# UnoRover.net
KiCad netlist of a schematic drawn in EAGLE
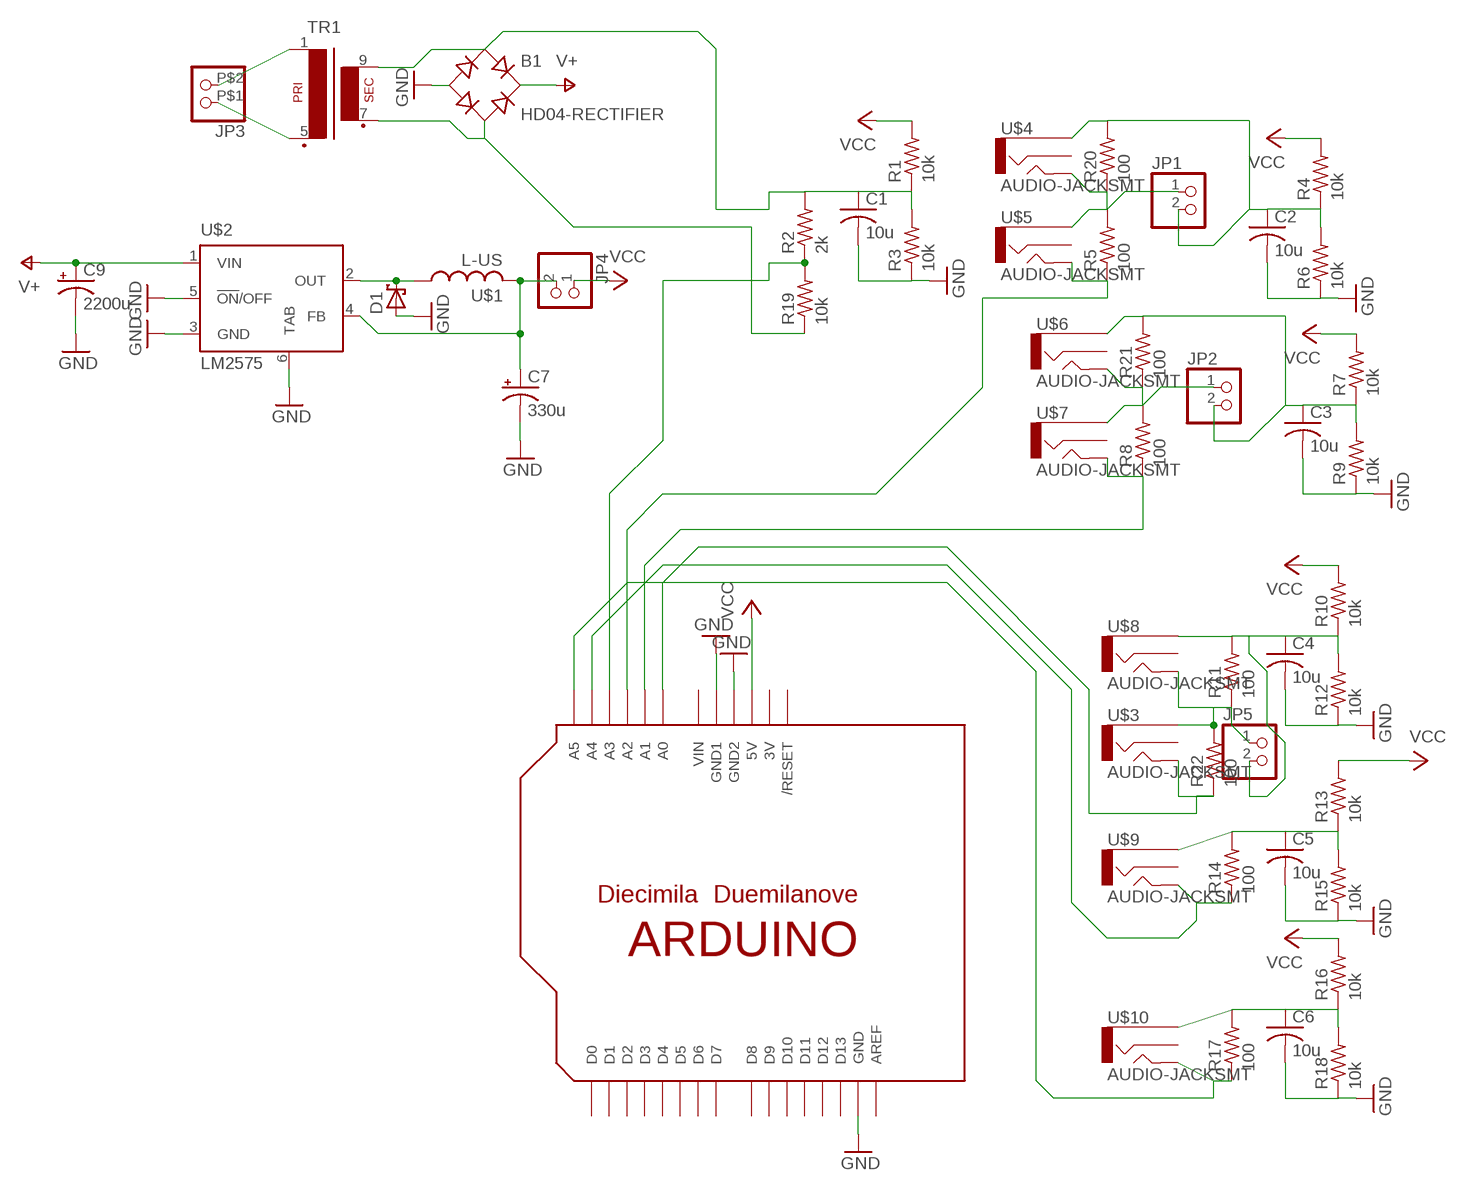
[diagram p0: schematic, sheet 1]

(export (version "E")
  (design (tool "Eeschema 10.0.6"))
  (components
    (comp (ref "B1")
      (value "HD04-RECTIFIER")
      (footprint "eagle-import:MINIDIP-4")
      (libsource (lib "eagle-import") (part "HD04-RECTIFIER"))
    )
    (comp (ref "C1")
      (value "10u")
      (footprint "eagle-import:C0805")
      (libsource (lib "eagle-import") (part "C-USC0805"))
    )
    (comp (ref "C2")
      (value "10u")
      (footprint "eagle-import:C0805")
      (libsource (lib "eagle-import") (part "C-USC0805"))
    )
    (comp (ref "C3")
      (value "10u")
      (footprint "eagle-import:C0805")
      (libsource (lib "eagle-import") (part "C-USC0805"))
    )
    (comp (ref "C4")
      (value "10u")
      (footprint "eagle-import:C0805")
      (libsource (lib "eagle-import") (part "C-USC0805"))
    )
    (comp (ref "C5")
      (value "10u")
      (footprint "eagle-import:C0805")
      (libsource (lib "eagle-import") (part "C-USC0805"))
    )
    (comp (ref "C6")
      (value "10u")
      (footprint "eagle-import:C0805")
      (libsource (lib "eagle-import") (part "C-USC0805"))
    )
    (comp (ref "C7")
      (value "330u")
      (footprint "eagle-import:E3,5-8")
      (libsource (lib "eagle-import") (part "CPOL-USE3.5-8"))
    )
    (comp (ref "C9")
      (value "2200u")
      (footprint "eagle-import:E5-13")
      (libsource (lib "eagle-import") (part "CPOL-USE5-13"))
    )
    (comp (ref "D1")
      (value "SCHOTTKY-DIODE")
      (footprint "eagle-import:SOD123FL")
      (libsource (lib "eagle-import") (part "SCHOTTKY-DIODE"))
    )
    (comp (ref "JP1")
      (value "PINHD-1X2")
      (footprint "eagle-import:1X02")
      (libsource (lib "eagle-import") (part "pinhead_PINHD-1X2"))
    )
    (comp (ref "JP2")
      (value "PINHD-1X2")
      (footprint "eagle-import:1X02")
      (libsource (lib "eagle-import") (part "pinhead_PINHD-1X2"))
    )
    (comp (ref "JP3")
      (value "PINHD-1X25MM_TERMINAL")
      (footprint "eagle-import:5MM_TERMINAL")
      (libsource (lib "eagle-import") (part "PINHD-1X25MM_TERMINAL"))
    )
    (comp (ref "JP4")
      (value "PINHD-1X2")
      (footprint "eagle-import:1X02")
      (libsource (lib "eagle-import") (part "PINHD-1X2"))
    )
    (comp (ref "JP5")
      (value "PINHD-1X2")
      (footprint "eagle-import:1X02")
      (libsource (lib "eagle-import") (part "pinhead_PINHD-1X2"))
    )
    (comp (ref "R1")
      (value "10k")
      (footprint "eagle-import:M0805")
      (libsource (lib "eagle-import") (part "R-US_M0805"))
    )
    (comp (ref "R2")
      (value "2k")
      (footprint "eagle-import:M0805")
      (libsource (lib "eagle-import") (part "R-US_M0805"))
    )
    (comp (ref "R3")
      (value "10k")
      (footprint "eagle-import:M0805")
      (libsource (lib "eagle-import") (part "R-US_M0805"))
    )
    (comp (ref "R4")
      (value "10k")
      (footprint "eagle-import:M0805")
      (libsource (lib "eagle-import") (part "R-US_M0805"))
    )
    (comp (ref "R5")
      (value "100")
      (footprint "eagle-import:M0805")
      (libsource (lib "eagle-import") (part "R-US_M0805"))
    )
    (comp (ref "R6")
      (value "10k")
      (footprint "eagle-import:M0805")
      (libsource (lib "eagle-import") (part "R-US_M0805"))
    )
    (comp (ref "R7")
      (value "10k")
      (footprint "eagle-import:M0805")
      (libsource (lib "eagle-import") (part "R-US_M0805"))
    )
    (comp (ref "R8")
      (value "100")
      (footprint "eagle-import:M0805")
      (libsource (lib "eagle-import") (part "R-US_M0805"))
    )
    (comp (ref "R9")
      (value "10k")
      (footprint "eagle-import:M0805")
      (libsource (lib "eagle-import") (part "R-US_M0805"))
    )
    (comp (ref "R10")
      (value "10k")
      (footprint "eagle-import:M0805")
      (libsource (lib "eagle-import") (part "R-US_M0805"))
    )
    (comp (ref "R11")
      (value "100")
      (footprint "eagle-import:M0805")
      (libsource (lib "eagle-import") (part "R-US_M0805"))
    )
    (comp (ref "R12")
      (value "10k")
      (footprint "eagle-import:M0805")
      (libsource (lib "eagle-import") (part "R-US_M0805"))
    )
    (comp (ref "R13")
      (value "10k")
      (footprint "eagle-import:M0805")
      (libsource (lib "eagle-import") (part "R-US_M0805"))
    )
    (comp (ref "R14")
      (value "100")
      (footprint "eagle-import:M0805")
      (libsource (lib "eagle-import") (part "R-US_M0805"))
    )
    (comp (ref "R15")
      (value "10k")
      (footprint "eagle-import:M0805")
      (libsource (lib "eagle-import") (part "R-US_M0805"))
    )
    (comp (ref "R16")
      (value "10k")
      (footprint "eagle-import:M0805")
      (libsource (lib "eagle-import") (part "R-US_M0805"))
    )
    (comp (ref "R17")
      (value "100")
      (footprint "eagle-import:M0805")
      (libsource (lib "eagle-import") (part "R-US_M0805"))
    )
    (comp (ref "R18")
      (value "10k")
      (footprint "eagle-import:M0805")
      (libsource (lib "eagle-import") (part "R-US_M0805"))
    )
    (comp (ref "R19")
      (value "10k")
      (footprint "eagle-import:M0805")
      (libsource (lib "eagle-import") (part "R-US_M0805"))
    )
    (comp (ref "R20")
      (value "100")
      (footprint "eagle-import:M0805")
      (libsource (lib "eagle-import") (part "R-US_M0805"))
    )
    (comp (ref "R21")
      (value "100")
      (footprint "eagle-import:M0805")
      (libsource (lib "eagle-import") (part "R-US_M0805"))
    )
    (comp (ref "R22")
      (value "100")
      (footprint "eagle-import:M0805")
      (libsource (lib "eagle-import") (part "R-US_M0805"))
    )
    (comp (ref "TR1")
      (value "EI30-1")
      (footprint "eagle-import:EI30-1")
      (libsource (lib "eagle-import") (part "EI30-1"))
    )
    (comp (ref "U$1")
      (value "L-US")
      (footprint "eagle-import:INDUCTOR_MURATA")
      (libsource (lib "eagle-import") (part "L-US"))
    )
    (comp (ref "U$2")
      (value "LM2575")
      (footprint "eagle-import:TO263-5")
      (libsource (lib "eagle-import") (part "LM2575"))
    )
    (comp (ref "U$3")
      (value "AUDIO-JACKSMT")
      (footprint "eagle-import:SJ-3523-SMT-JACK")
      (libsource (lib "eagle-import") (part "AUDIO-JACKSMT"))
    )
    (comp (ref "U$4")
      (value "AUDIO-JACKSMT")
      (footprint "eagle-import:SJ-3523-SMT-JACK")
      (libsource (lib "eagle-import") (part "AUDIO-JACKSMT"))
    )
    (comp (ref "U$5")
      (value "AUDIO-JACKSMT")
      (footprint "eagle-import:SJ-3523-SMT-JACK")
      (libsource (lib "eagle-import") (part "AUDIO-JACKSMT"))
    )
    (comp (ref "U$6")
      (value "AUDIO-JACKSMT")
      (footprint "eagle-import:SJ-3523-SMT-JACK")
      (libsource (lib "eagle-import") (part "AUDIO-JACKSMT"))
    )
    (comp (ref "U$7")
      (value "AUDIO-JACKSMT")
      (footprint "eagle-import:SJ-3523-SMT-JACK")
      (libsource (lib "eagle-import") (part "AUDIO-JACKSMT"))
    )
    (comp (ref "U$8")
      (value "AUDIO-JACKSMT")
      (footprint "eagle-import:SJ-3523-SMT-JACK")
      (libsource (lib "eagle-import") (part "AUDIO-JACKSMT"))
    )
    (comp (ref "U$9")
      (value "AUDIO-JACKSMT")
      (footprint "eagle-import:SJ-3523-SMT-JACK")
      (libsource (lib "eagle-import") (part "AUDIO-JACKSMT"))
    )
    (comp (ref "U$10")
      (value "AUDIO-JACKSMT")
      (footprint "eagle-import:SJ-3523-SMT-JACK")
      (libsource (lib "eagle-import") (part "AUDIO-JACKSMT"))
    )
    (comp (ref "U$11")
      (value "ARDUINODUEMILANOVE")
      (footprint "eagle-import:ARDUINO")
      (libsource (lib "eagle-import") (part "ARDUINODUEMILANOVE"))
    )
  )
  (nets
    (net (code "1") (name "/3V") (class "Default")
      (node (ref "U$11") (pin "3V") (pinfunction "3V_3V") (pintype "power_in"))
    )
    (net (code "2") (name "/VIN") (class "Default")
      (node (ref "U$11") (pin "VIN") (pinfunction "VIN_VIN") (pintype "power_in"))
    )
    (net (code "3") (name "GND") (class "Default")
      (node (ref "B1") (pin "P$4") (pinfunction "-_P$4") (pintype "passive"))
      (node (ref "C1") (pin "2") (pinfunction "2_2") (pintype "passive"))
      (node (ref "C2") (pin "2") (pinfunction "2_2") (pintype "passive"))
      (node (ref "C3") (pin "2") (pinfunction "2_2") (pintype "passive"))
      (node (ref "C4") (pin "2") (pinfunction "2_2") (pintype "passive"))
      (node (ref "C5") (pin "2") (pinfunction "2_2") (pintype "passive"))
      (node (ref "C6") (pin "2") (pinfunction "2_2") (pintype "passive"))
      (node (ref "C7") (pin "-") (pinfunction "-_-") (pintype "passive"))
      (node (ref "C9") (pin "-") (pinfunction "-_-") (pintype "passive"))
      (node (ref "D1") (pin "A") (pinfunction "A_A") (pintype "passive"))
      (node (ref "R12") (pin "1") (pinfunction "1_1") (pintype "passive"))
      (node (ref "R15") (pin "1") (pinfunction "1_1") (pintype "passive"))
      (node (ref "R18") (pin "1") (pinfunction "1_1") (pintype "passive"))
      (node (ref "R3") (pin "1") (pinfunction "1_1") (pintype "passive"))
      (node (ref "R6") (pin "1") (pinfunction "1_1") (pintype "passive"))
      (node (ref "R9") (pin "1") (pinfunction "1_1") (pintype "passive"))
      (node (ref "U$11") (pin "GND") (pinfunction "GND_GND") (pintype "power_in"))
      (node (ref "U$11") (pin "GND1") (pinfunction "GND1_GND1") (pintype "power_in"))
      (node (ref "U$11") (pin "GND2") (pinfunction "GND2_GND2") (pintype "power_in"))
      (node (ref "U$2") (pin "3") (pinfunction "GND_3") (pintype "power_in"))
      (node (ref "U$2") (pin "5") (pinfunction "~{ON}/OFF_5") (pintype "input"))
      (node (ref "U$2") (pin "6") (pinfunction "TAB_6") (pintype "power_in"))
    )
    (net (code "4") (name "Net-(B1-AC1)") (class "Default")
      (node (ref "B1") (pin "P$1") (pinfunction "AC1_P$1") (pintype "passive"))
      (node (ref "C1") (pin "1") (pinfunction "1_1") (pintype "passive"))
      (node (ref "R1") (pin "1") (pinfunction "1_1") (pintype "passive"))
      (node (ref "R2") (pin "2") (pinfunction "2_2") (pintype "passive"))
      (node (ref "R3") (pin "2") (pinfunction "2_2") (pintype "passive"))
      (node (ref "TR1") (pin "9") (pinfunction "S4_9") (pintype "passive"))
    )
    (net (code "5") (name "Net-(B1-AC2)") (class "Default")
      (node (ref "B1") (pin "P$2") (pinfunction "AC2_P$2") (pintype "passive"))
      (node (ref "R19") (pin "1") (pinfunction "1_1") (pintype "passive"))
      (node (ref "TR1") (pin "7") (pinfunction "S3_7") (pintype "passive"))
    )
    (net (code "6") (name "Net-(JP3-1)") (class "Default")
      (node (ref "JP3") (pin "P$1") (pinfunction "1_P$1") (pintype "passive"))
      (node (ref "TR1") (pin "5") (pinfunction "P2_5") (pintype "passive"))
    )
    (net (code "7") (name "Net-(JP3-2)") (class "Default")
      (node (ref "JP3") (pin "P$2") (pinfunction "2_P$2") (pintype "passive"))
      (node (ref "TR1") (pin "1") (pinfunction "P1_1") (pintype "passive"))
    )
    (net (code "8") (name "Net-(R19-Pad2)") (class "Default")
      (node (ref "R19") (pin "2") (pinfunction "2_2") (pintype "passive"))
      (node (ref "R2") (pin "1") (pinfunction "1_1") (pintype "passive"))
      (node (ref "U$11") (pin "A3") (pinfunction "A3_A3") (pintype "bidirectional"))
    )
    (net (code "9") (name "Net-(U$1-1)") (class "Default")
      (node (ref "D1") (pin "C") (pinfunction "C_C") (pintype "passive"))
      (node (ref "U$1") (pin "P$1") (pinfunction "1_P$1") (pintype "passive"))
      (node (ref "U$2") (pin "2") (pinfunction "OUT_2") (pintype "output"))
    )
    (net (code "10") (name "Net-(U$1-2)") (class "Default")
      (node (ref "C7") (pin "+") (pinfunction "+_+") (pintype "passive"))
      (node (ref "JP4") (pin "2") (pinfunction "2_2") (pintype "passive"))
      (node (ref "U$1") (pin "P$3") (pinfunction "2_P$3") (pintype "passive"))
      (node (ref "U$2") (pin "4") (pinfunction "FB_4") (pintype "input"))
    )
    (net (code "11") (name "Net-(U$3-1)") (class "Default")
      (node (ref "JP5") (pin "1") (pinfunction "1_1") (pintype "passive"))
      (node (ref "R11") (pin "1") (pinfunction "1_1") (pintype "passive"))
      (node (ref "R22") (pin "2") (pinfunction "2_2") (pintype "passive"))
      (node (ref "U$3") (pin "P$1") (pinfunction "1_P$1") (pintype "bidirectional"))
      (node (ref "U$8") (pin "P$2") (pinfunction "5_P$2") (pintype "bidirectional"))
    )
    (net (code "12") (name "Net-(U$3-5)") (class "Default")
      (node (ref "R22") (pin "1") (pinfunction "1_1") (pintype "passive"))
      (node (ref "U$11") (pin "A0") (pinfunction "A0_A0") (pintype "bidirectional"))
      (node (ref "U$3") (pin "P$2") (pinfunction "5_P$2") (pintype "bidirectional"))
    )
    (net (code "13") (name "Net-(U$4-1)") (class "Default")
      (node (ref "C2") (pin "1") (pinfunction "1_1") (pintype "passive"))
      (node (ref "JP1") (pin "2") (pinfunction "2_2") (pintype "passive"))
      (node (ref "R20") (pin "2") (pinfunction "2_2") (pintype "passive"))
      (node (ref "R4") (pin "1") (pinfunction "1_1") (pintype "passive"))
      (node (ref "R6") (pin "2") (pinfunction "2_2") (pintype "passive"))
      (node (ref "U$4") (pin "P$1") (pinfunction "1_P$1") (pintype "bidirectional"))
    )
    (net (code "14") (name "Net-(U$4-5)") (class "Default")
      (node (ref "JP1") (pin "1") (pinfunction "1_1") (pintype "passive"))
      (node (ref "R20") (pin "1") (pinfunction "1_1") (pintype "passive"))
      (node (ref "R5") (pin "2") (pinfunction "2_2") (pintype "passive"))
      (node (ref "U$4") (pin "P$2") (pinfunction "5_P$2") (pintype "bidirectional"))
      (node (ref "U$5") (pin "P$1") (pinfunction "1_P$1") (pintype "bidirectional"))
    )
    (net (code "15") (name "Net-(U$5-5)") (class "Default")
      (node (ref "R5") (pin "1") (pinfunction "1_1") (pintype "passive"))
      (node (ref "U$11") (pin "A2") (pinfunction "A2_A2") (pintype "bidirectional"))
      (node (ref "U$5") (pin "P$2") (pinfunction "5_P$2") (pintype "bidirectional"))
    )
    (net (code "16") (name "Net-(U$6-1)") (class "Default")
      (node (ref "C3") (pin "1") (pinfunction "1_1") (pintype "passive"))
      (node (ref "JP2") (pin "2") (pinfunction "2_2") (pintype "passive"))
      (node (ref "R21") (pin "2") (pinfunction "2_2") (pintype "passive"))
      (node (ref "R7") (pin "1") (pinfunction "1_1") (pintype "passive"))
      (node (ref "R9") (pin "2") (pinfunction "2_2") (pintype "passive"))
      (node (ref "U$6") (pin "P$1") (pinfunction "1_P$1") (pintype "bidirectional"))
    )
    (net (code "17") (name "Net-(U$6-5)") (class "Default")
      (node (ref "JP2") (pin "1") (pinfunction "1_1") (pintype "passive"))
      (node (ref "R21") (pin "1") (pinfunction "1_1") (pintype "passive"))
      (node (ref "R8") (pin "2") (pinfunction "2_2") (pintype "passive"))
      (node (ref "U$6") (pin "P$2") (pinfunction "5_P$2") (pintype "bidirectional"))
      (node (ref "U$7") (pin "P$1") (pinfunction "1_P$1") (pintype "bidirectional"))
    )
    (net (code "18") (name "Net-(U$7-5)") (class "Default")
      (node (ref "R8") (pin "1") (pinfunction "1_1") (pintype "passive"))
      (node (ref "U$11") (pin "A1") (pinfunction "A1_A1") (pintype "bidirectional"))
      (node (ref "U$7") (pin "P$2") (pinfunction "5_P$2") (pintype "bidirectional"))
    )
    (net (code "19") (name "Net-(U$8-1)") (class "Default")
      (node (ref "C4") (pin "1") (pinfunction "1_1") (pintype "passive"))
      (node (ref "JP5") (pin "2") (pinfunction "2_2") (pintype "passive"))
      (node (ref "R10") (pin "1") (pinfunction "1_1") (pintype "passive"))
      (node (ref "R11") (pin "2") (pinfunction "2_2") (pintype "passive"))
      (node (ref "R12") (pin "2") (pinfunction "2_2") (pintype "passive"))
      (node (ref "U$8") (pin "P$1") (pinfunction "1_P$1") (pintype "bidirectional"))
    )
    (net (code "20") (name "Net-(U$9-1)") (class "Default")
      (node (ref "C5") (pin "1") (pinfunction "1_1") (pintype "passive"))
      (node (ref "R13") (pin "1") (pinfunction "1_1") (pintype "passive"))
      (node (ref "R14") (pin "2") (pinfunction "2_2") (pintype "passive"))
      (node (ref "R15") (pin "2") (pinfunction "2_2") (pintype "passive"))
      (node (ref "U$9") (pin "P$1") (pinfunction "1_P$1") (pintype "bidirectional"))
    )
    (net (code "21") (name "Net-(U$9-5)") (class "Default")
      (node (ref "R14") (pin "1") (pinfunction "1_1") (pintype "passive"))
      (node (ref "U$11") (pin "A4") (pinfunction "A4_A4") (pintype "bidirectional"))
      (node (ref "U$9") (pin "P$2") (pinfunction "5_P$2") (pintype "bidirectional"))
    )
    (net (code "22") (name "Net-(U$10-1)") (class "Default")
      (node (ref "C6") (pin "1") (pinfunction "1_1") (pintype "passive"))
      (node (ref "R16") (pin "1") (pinfunction "1_1") (pintype "passive"))
      (node (ref "R17") (pin "2") (pinfunction "2_2") (pintype "passive"))
      (node (ref "R18") (pin "2") (pinfunction "2_2") (pintype "passive"))
      (node (ref "U$10") (pin "P$1") (pinfunction "1_P$1") (pintype "bidirectional"))
    )
    (net (code "23") (name "Net-(U$10-5)") (class "Default")
      (node (ref "R17") (pin "1") (pinfunction "1_1") (pintype "passive"))
      (node (ref "U$10") (pin "P$2") (pinfunction "5_P$2") (pintype "bidirectional"))
      (node (ref "U$11") (pin "A5") (pinfunction "A5_A5") (pintype "bidirectional"))
    )
    (net (code "24") (name "V+") (class "Default")
      (node (ref "B1") (pin "P$3") (pinfunction "+_P$3") (pintype "passive"))
      (node (ref "C9") (pin "+") (pinfunction "+_+") (pintype "passive"))
      (node (ref "U$2") (pin "1") (pinfunction "VIN_1") (pintype "input"))
    )
    (net (code "25") (name "VCC") (class "Default")
      (node (ref "JP4") (pin "1") (pinfunction "1_1") (pintype "passive"))
      (node (ref "R1") (pin "2") (pinfunction "2_2") (pintype "passive"))
      (node (ref "R10") (pin "2") (pinfunction "2_2") (pintype "passive"))
      (node (ref "R13") (pin "2") (pinfunction "2_2") (pintype "passive"))
      (node (ref "R16") (pin "2") (pinfunction "2_2") (pintype "passive"))
      (node (ref "R4") (pin "2") (pinfunction "2_2") (pintype "passive"))
      (node (ref "R7") (pin "2") (pinfunction "2_2") (pintype "passive"))
      (node (ref "U$11") (pin "5V") (pinfunction "5V_5V") (pintype "power_in"))
    )
    (net (code "26") (name "unconnected-(U$3-2-PadP$3)") (class "Default")
      (node (ref "U$3") (pin "P$3") (pinfunction "2_P$3") (pintype "bidirectional"))
    )
    (net (code "27") (name "unconnected-(U$4-2-PadP$3)") (class "Default")
      (node (ref "U$4") (pin "P$3") (pinfunction "2_P$3") (pintype "bidirectional"))
    )
    (net (code "28") (name "unconnected-(U$5-2-PadP$3)") (class "Default")
      (node (ref "U$5") (pin "P$3") (pinfunction "2_P$3") (pintype "bidirectional"))
    )
    (net (code "29") (name "unconnected-(U$6-2-PadP$3)") (class "Default")
      (node (ref "U$6") (pin "P$3") (pinfunction "2_P$3") (pintype "bidirectional"))
    )
    (net (code "30") (name "unconnected-(U$7-2-PadP$3)") (class "Default")
      (node (ref "U$7") (pin "P$3") (pinfunction "2_P$3") (pintype "bidirectional"))
    )
    (net (code "31") (name "unconnected-(U$8-2-PadP$3)") (class "Default")
      (node (ref "U$8") (pin "P$3") (pinfunction "2_P$3") (pintype "bidirectional"))
    )
    (net (code "32") (name "unconnected-(U$9-2-PadP$3)") (class "Default")
      (node (ref "U$9") (pin "P$3") (pinfunction "2_P$3") (pintype "bidirectional"))
    )
    (net (code "33") (name "unconnected-(U$10-2-PadP$3)") (class "Default")
      (node (ref "U$10") (pin "P$3") (pinfunction "2_P$3") (pintype "bidirectional"))
    )
    (net (code "34") (name "unconnected-(U$11-PadAREF)") (class "Default")
      (node (ref "U$11") (pin "AREF") (pinfunction "AREF_AREF") (pintype "bidirectional"))
    )
    (net (code "35") (name "unconnected-(U$11-PadD0)") (class "Default")
      (node (ref "U$11") (pin "D0") (pinfunction "D0_D0") (pintype "bidirectional"))
    )
    (net (code "36") (name "unconnected-(U$11-PadD1)") (class "Default")
      (node (ref "U$11") (pin "D1") (pinfunction "D1_D1") (pintype "bidirectional"))
    )
    (net (code "37") (name "unconnected-(U$11-PadD2)") (class "Default")
      (node (ref "U$11") (pin "D2") (pinfunction "D2_D2") (pintype "bidirectional"))
    )
    (net (code "38") (name "unconnected-(U$11-PadD3)") (class "Default")
      (node (ref "U$11") (pin "D3") (pinfunction "D3_D3") (pintype "bidirectional"))
    )
    (net (code "39") (name "unconnected-(U$11-PadD4)") (class "Default")
      (node (ref "U$11") (pin "D4") (pinfunction "D4_D4") (pintype "bidirectional"))
    )
    (net (code "40") (name "unconnected-(U$11-PadD5)") (class "Default")
      (node (ref "U$11") (pin "D5") (pinfunction "D5_D5") (pintype "bidirectional"))
    )
    (net (code "41") (name "unconnected-(U$11-PadD6)") (class "Default")
      (node (ref "U$11") (pin "D6") (pinfunction "D6_D6") (pintype "bidirectional"))
    )
    (net (code "42") (name "unconnected-(U$11-PadD7)") (class "Default")
      (node (ref "U$11") (pin "D7") (pinfunction "D7_D7") (pintype "bidirectional"))
    )
    (net (code "43") (name "unconnected-(U$11-PadD8)") (class "Default")
      (node (ref "U$11") (pin "D8") (pinfunction "D8_D8") (pintype "bidirectional"))
    )
    (net (code "44") (name "unconnected-(U$11-PadD9)") (class "Default")
      (node (ref "U$11") (pin "D9") (pinfunction "D9_D9") (pintype "bidirectional"))
    )
    (net (code "45") (name "unconnected-(U$11-PadD10)") (class "Default")
      (node (ref "U$11") (pin "D10") (pinfunction "D10_D10") (pintype "bidirectional"))
    )
    (net (code "46") (name "unconnected-(U$11-PadD11)") (class "Default")
      (node (ref "U$11") (pin "D11") (pinfunction "D11_D11") (pintype "bidirectional"))
    )
    (net (code "47") (name "unconnected-(U$11-PadD12)") (class "Default")
      (node (ref "U$11") (pin "D12") (pinfunction "D12_D12") (pintype "bidirectional"))
    )
    (net (code "48") (name "unconnected-(U$11-PadD13)") (class "Default")
      (node (ref "U$11") (pin "D13") (pinfunction "D13_D13") (pintype "bidirectional"))
    )
    (net (code "49") (name "unconnected-(U$11-{slash}RESET-PadRESET)") (class "Default")
      (node (ref "U$11") (pin "RESET") (pinfunction "/RESET_RESET") (pintype "bidirectional"))
    )
  )
)
